# WPT_Round_2_RX_Schematics.net
KiCad netlist of a schematic drawn in Altium Designer
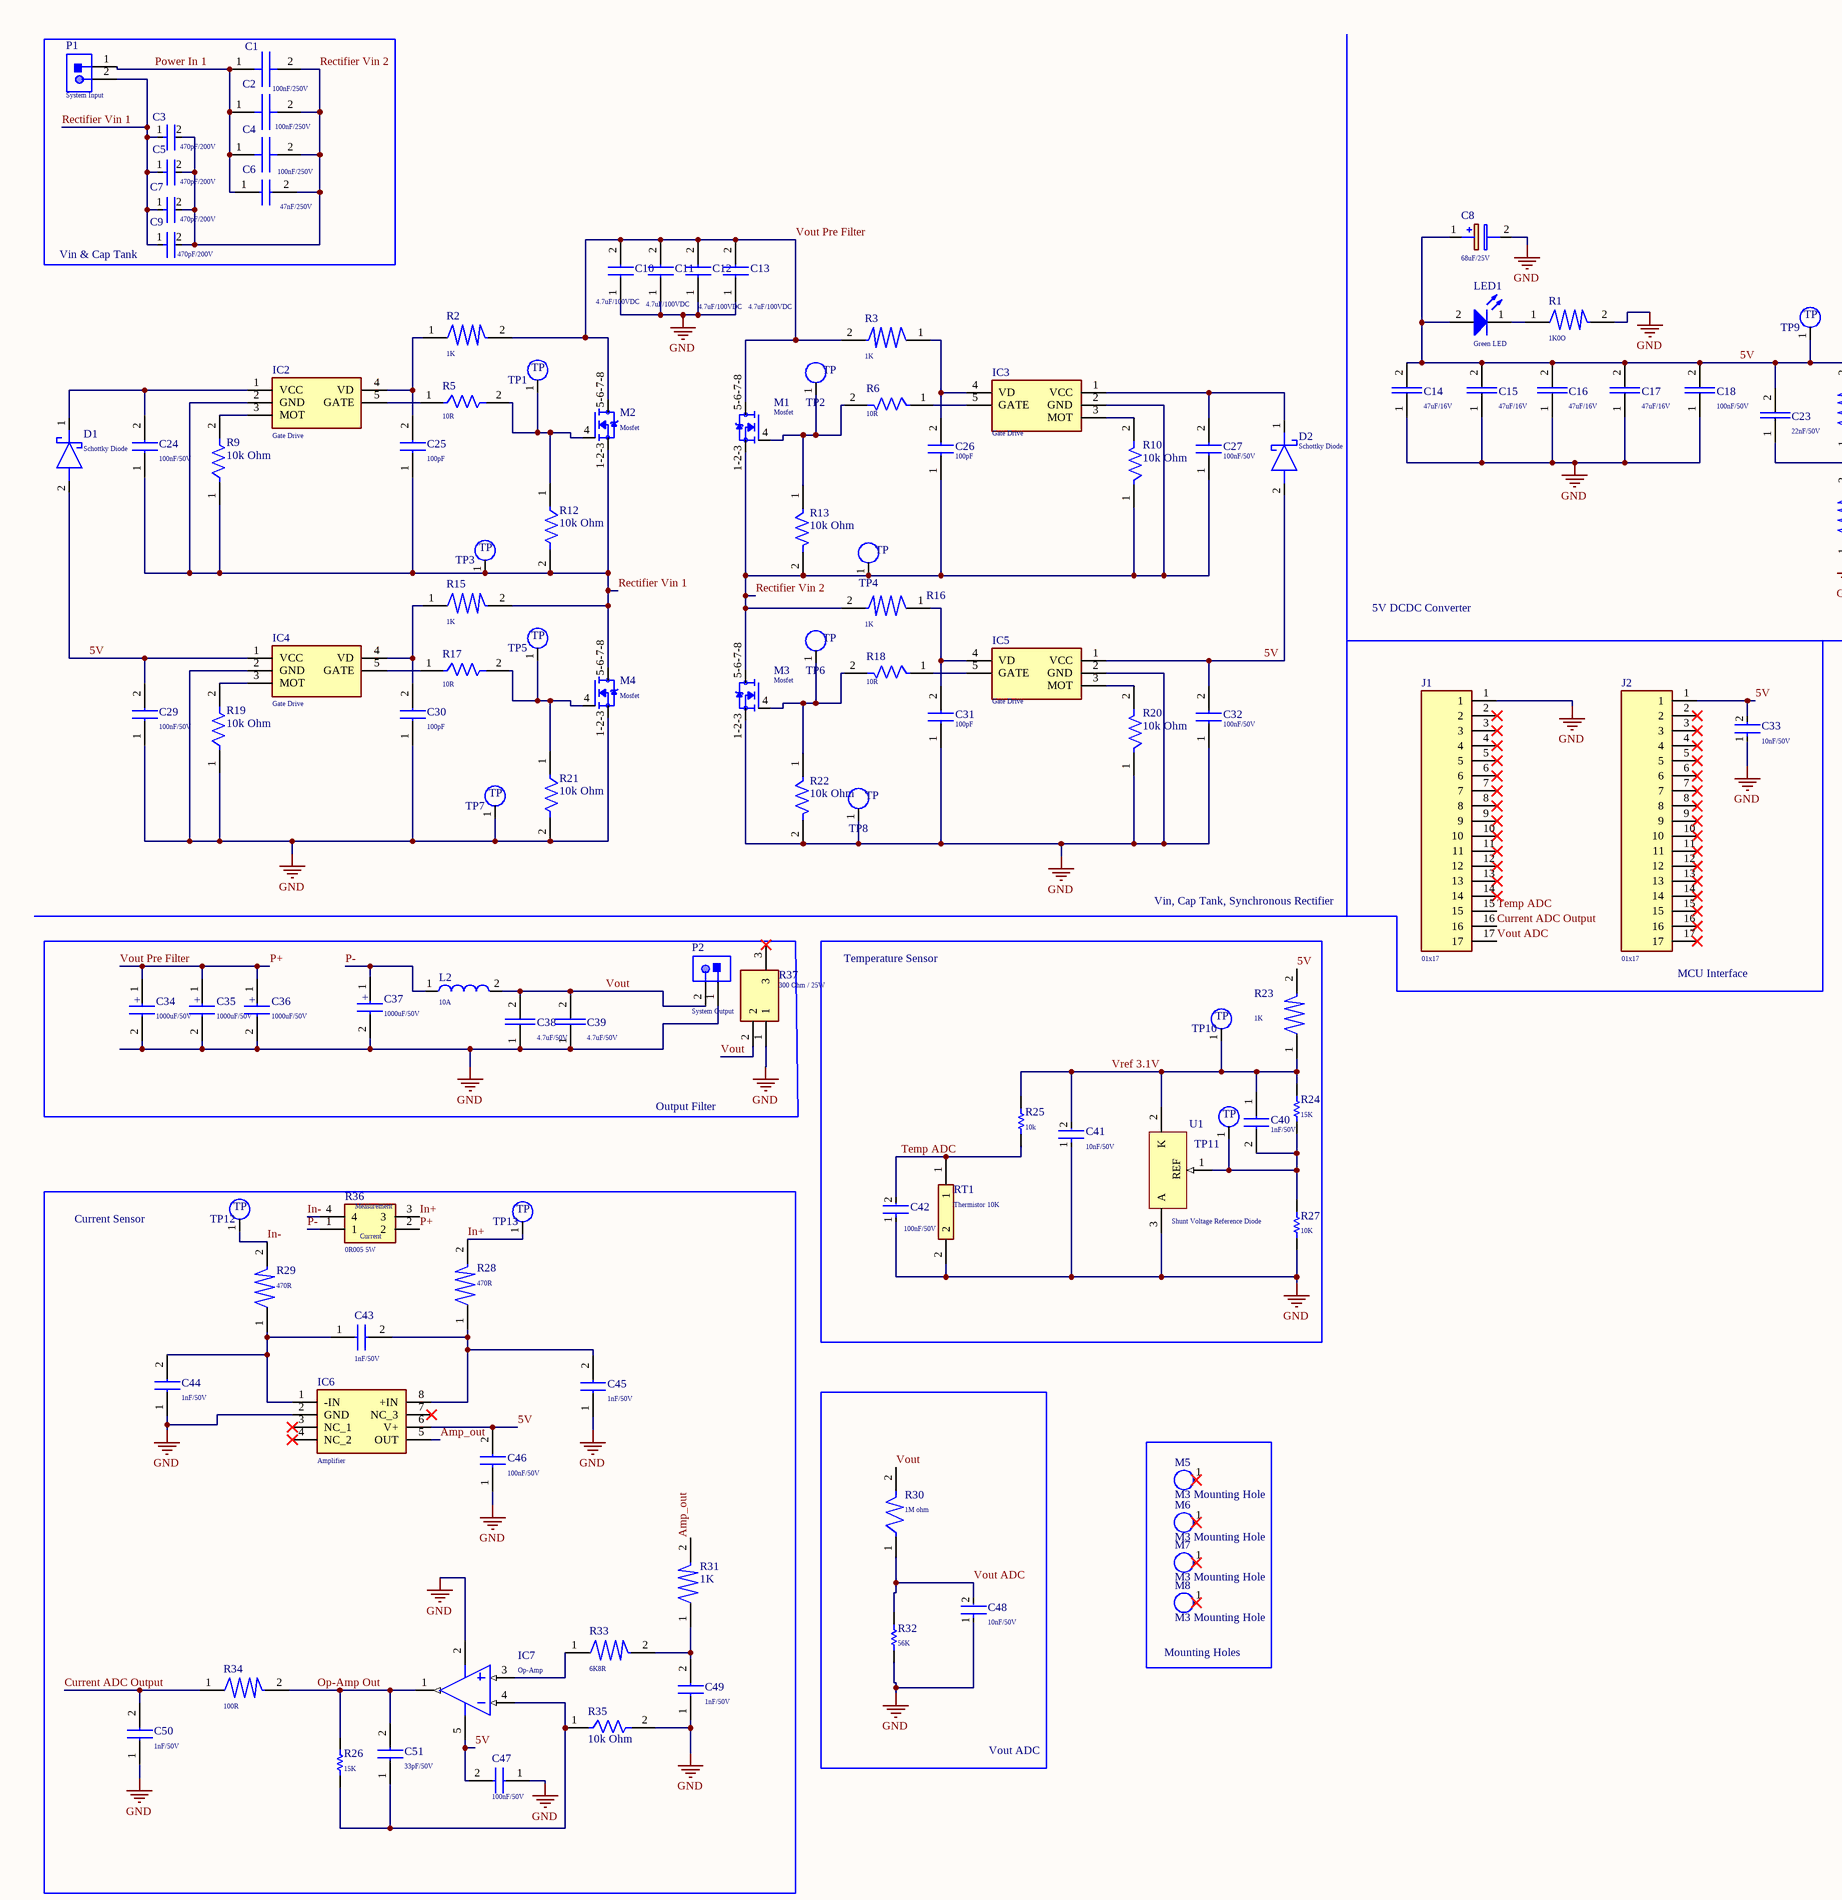
[diagram p0: WPT Round 2 RX Schematics.SchDoc, left]
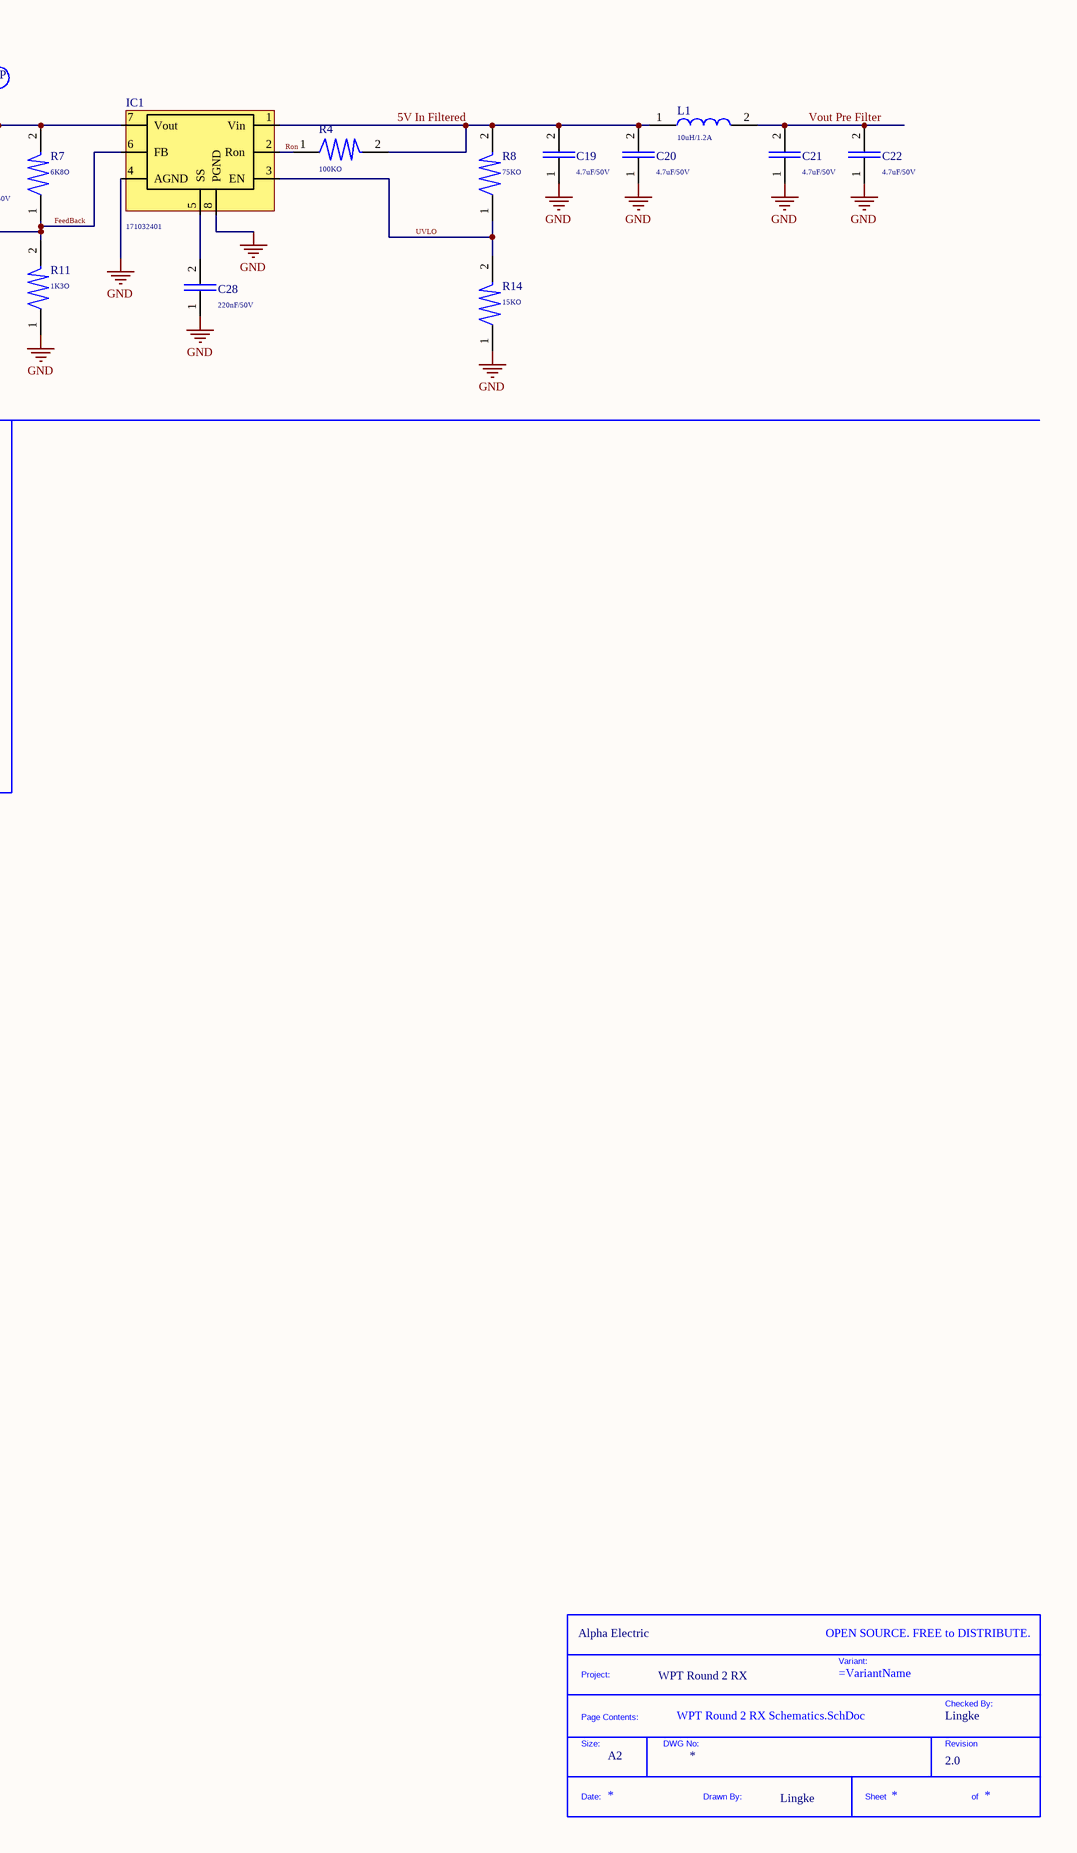
[diagram p1: WPT Round 2 RX Schematics.SchDoc, right]

(export (version "E")
  (design (tool "Eeschema 10.0.6"))
  (components
    (comp (ref "*")
      (value "Title_Block")
      (description "Standard Title Block.")
      (fields
        (field (name "PROJECT NAME") "WPT Round 2 RX")
        (field (name "COMPANY") "Alpha Electric")
        (field (name "DRAWN BY") "Lingke")
        (field (name "REVISION") "2.0")
        (field (name "DWG NO") "*")
        (field (name "SIZE") "A2")
        (field (name "CHECKED BY") "Lingke")
      )
      (libsource (lib "Symbol Library") (part "Title_Block"))
    )
    (comp (ref "C1")
      (value "100nF/250V")
      (footprint "SamacSys:CAPC4532X220N")
      (fields (field (name "MANUFACTURER_PART_NUMBER") "C1812C104JAGACAUTO"))
      (libsource (lib "Symbol Library") (part "C1812C104JAGACAUTO"))
    )
    (comp (ref "C2")
      (value "100nF/250V")
      (footprint "SamacSys:CAPC4532X220N")
      (fields (field (name "MANUFACTURER_PART_NUMBER") "C1812C104JAGACAUTO"))
      (libsource (lib "Symbol Library") (part "C1812C104JAGACAUTO"))
    )
    (comp (ref "C3")
      (value "470pF/200V")
      (footprint "FP-C1206C-EB-MFG")
      (description "CAP CER 470PF 200V 10% NP0 1206")
      (fields
        (field (name "OCTOPART") "https://octopart.com/c1206c471k2gactu-kemet-3658280")
        (field (name "TOLERANCE") "0.1")
      )
      (libsource (lib "Symbol Library") (part "C1206C471K2GACTU"))
    )
    (comp (ref "C4")
      (value "100nF/250V")
      (footprint "SamacSys:CAPC4532X220N")
      (fields (field (name "MANUFACTURER_PART_NUMBER") "C1812C104JAGACAUTO"))
      (libsource (lib "Symbol Library") (part "C1812C104JAGACAUTO"))
    )
    (comp (ref "C5")
      (value "470pF/200V")
      (footprint "FP-C1206C-EB-MFG")
      (description "CAP CER 470PF 200V 10% NP0 1206")
      (fields
        (field (name "OCTOPART") "https://octopart.com/c1206c471k2gactu-kemet-3658280")
        (field (name "TOLERANCE") "0.1")
      )
      (libsource (lib "Symbol Library") (part "C1206C471K2GACTU"))
    )
    (comp (ref "C6")
      (value "47nF/250V")
      (footprint "SamacSys:CAPC4532X350N")
      (description "Capacitor\r\n47nF/250V \r\nC0G")
      (fields (field (name "MANUFACTURER_PART_NUMBER") "C4532C0G2E473J320KA"))
      (libsource (lib "Symbol Library") (part "C4532C0G2E473J320KA"))
    )
    (comp (ref "C7")
      (value "470pF/200V")
      (footprint "FP-C1206C-EB-MFG")
      (description "CAP CER 470PF 200V 10% NP0 1206")
      (fields
        (field (name "OCTOPART") "https://octopart.com/c1206c471k2gactu-kemet-3658280")
        (field (name "TOLERANCE") "0.1")
      )
      (libsource (lib "Symbol Library") (part "C1206C471K2GACTU"))
    )
    (comp (ref "C8")
      (value "68uF/25V")
      (footprint "SamacSys:CAPAE830X1170N")
      (description "Capacitor Polarised")
      (fields (field (name "MANUFACTURER_PART_NUMBER") "875075555003"))
      (libsource (lib "Symbol Library") (part "875075555003"))
    )
    (comp (ref "C9")
      (value "470pF/200V")
      (footprint "FP-C1206C-EB-MFG")
      (description "CAP CER 470PF 200V 10% NP0 1206")
      (fields
        (field (name "OCTOPART") "https://octopart.com/c1206c471k2gactu-kemet-3658280")
        (field (name "TOLERANCE") "0.1")
      )
      (libsource (lib "Symbol Library") (part "C1206C471K2GACTU"))
    )
    (comp (ref "C10")
      (value "4.7uF/100VDC")
      (footprint "SamacSys:CAPC3225X280N")
      (fields
        (field (name "MOUSER2 PART NUMBER") "810-CNC6P1X7R2A475K2")
        (field (name "MANUFACTURER_PART_NUMBER") "CNC6P1X7R2A475K250AE")
      )
      (libsource (lib "Symbol Library") (part "CNC6P1X7R2A475K250AE"))
    )
    (comp (ref "C11")
      (value "4.7uF/100VDC")
      (footprint "SamacSys:CAPC3225X280N")
      (fields
        (field (name "MOUSER2 PART NUMBER") "810-CNC6P1X7R2A475K2")
        (field (name "MANUFACTURER_PART_NUMBER") "CNC6P1X7R2A475K250AE")
      )
      (libsource (lib "Symbol Library") (part "CNC6P1X7R2A475K250AE"))
    )
    (comp (ref "C12")
      (value "4.7uF/100VDC")
      (footprint "SamacSys:CAPC3225X280N")
      (fields
        (field (name "MOUSER2 PART NUMBER") "810-CNC6P1X7R2A475K2")
        (field (name "MANUFACTURER_PART_NUMBER") "CNC6P1X7R2A475K250AE")
      )
      (libsource (lib "Symbol Library") (part "CNC6P1X7R2A475K250AE"))
    )
    (comp (ref "C13")
      (value "4.7uF/100VDC")
      (footprint "SamacSys:CAPC3225X280N")
      (fields
        (field (name "MOUSER2 PART NUMBER") "810-CNC6P1X7R2A475K2")
        (field (name "MANUFACTURER_PART_NUMBER") "CNC6P1X7R2A475K250AE")
      )
      (libsource (lib "Symbol Library") (part "CNC6P1X7R2A475K250AE"))
    )
    (comp (ref "C14")
      (value "47uF/16V")
      (footprint "SamacSys:CAPC3225X280N")
      (description "Capacitor 47uF/16V")
      (libsource (lib "Symbol Library") (part "EMK325ABJ476MMHP"))
    )
    (comp (ref "C15")
      (value "47uF/16V")
      (footprint "SamacSys:CAPC3225X280N")
      (description "Capacitor 47uF/16V")
      (libsource (lib "Symbol Library") (part "EMK325ABJ476MMHP"))
    )
    (comp (ref "C16")
      (value "47uF/16V")
      (footprint "SamacSys:CAPC3225X280N")
      (description "Capacitor 47uF/16V")
      (libsource (lib "Symbol Library") (part "EMK325ABJ476MMHP"))
    )
    (comp (ref "C17")
      (value "47uF/16V")
      (footprint "SamacSys:CAPC3225X280N")
      (description "Capacitor 47uF/16V")
      (libsource (lib "Symbol Library") (part "EMK325ABJ476MMHP"))
    )
    (comp (ref "C18")
      (value "100nF/50V")
      (footprint "SamacSys:CAPC3216X90N")
      (description "Capacitor 100nF/50V")
      (fields
        (field (name "MOUSER2 PART NUMBER") "710-885012208087")
        (field (name "MANUFACTURER_PART_NUMBER") "885012208087")
      )
      (libsource (lib "Symbol Library") (part "885012208087"))
    )
    (comp (ref "C19")
      (value "4.7uF/50V")
      (footprint "SamacSys:CAPC3225X280N")
      (description "Capacitor 4.7uF/50V")
      (fields (field (name "MANUFACTURER_PART_NUMBER") "885012209048"))
      (libsource (lib "Symbol Library") (part "885012209048"))
    )
    (comp (ref "C20")
      (value "4.7uF/50V")
      (footprint "SamacSys:CAPC3225X280N")
      (description "Capacitor 4.7uF/50V")
      (fields (field (name "MANUFACTURER_PART_NUMBER") "885012209048"))
      (libsource (lib "Symbol Library") (part "885012209048"))
    )
    (comp (ref "C21")
      (value "4.7uF/50V")
      (footprint "SamacSys:CAPC3225X280N")
      (description "Capacitor 4.7uF/50V")
      (fields (field (name "MANUFACTURER_PART_NUMBER") "885012209048"))
      (libsource (lib "Symbol Library") (part "885012209048"))
    )
    (comp (ref "C22")
      (value "4.7uF/50V")
      (footprint "SamacSys:CAPC3225X280N")
      (description "Capacitor 4.7uF/50V")
      (fields (field (name "MANUFACTURER_PART_NUMBER") "885012209048"))
      (libsource (lib "Symbol Library") (part "885012209048"))
    )
    (comp (ref "C23")
      (value "22nF/50V")
      (footprint "SamacSys:CAPC2012X90N")
      (description "Capacitor 22nF/50V")
      (fields
        (field (name "MOUSER2 PART NUMBER") "710-885012207094")
        (field (name "MANUFACTURER_PART_NUMBER") "885012207094")
      )
      (libsource (lib "Symbol Library") (part "885012207094"))
    )
    (comp (ref "C24")
      (value "100nF/50V")
      (footprint "SamacSys:CAPC2012X90N")
      (description "Capacitor 100nF/50V")
      (fields
        (field (name "MOUSER2 PART NUMBER") "710-885012207098")
        (field (name "MANUFACTURER_PART_NUMBER") "885012207098")
      )
      (libsource (lib "") (part "885012207098_1"))
    )
    (comp (ref "C25")
      (value "100pF")
      (footprint "SamacSys:CAPC2012X70N")
      (description "Capacitor 100pF")
      (fields (field (name "MANUFACTURER_PART_NUMBER") "885012007057"))
      (libsource (lib "") (part "885012007057_1"))
    )
    (comp (ref "C26")
      (value "100pF")
      (footprint "SamacSys:CAPC2012X70N")
      (description "Capacitor 100pF")
      (fields (field (name "MANUFACTURER_PART_NUMBER") "885012007057"))
      (libsource (lib "") (part "885012007057_1"))
    )
    (comp (ref "C27")
      (value "100nF/50V")
      (footprint "SamacSys:CAPC2012X90N")
      (description "Capacitor 100nF/50V")
      (fields
        (field (name "MOUSER2 PART NUMBER") "710-885012207098")
        (field (name "MANUFACTURER_PART_NUMBER") "885012207098")
      )
      (libsource (lib "") (part "885012207098_1"))
    )
    (comp (ref "C28")
      (value "220nF/50V")
      (footprint "SamacSys:CAPC2012X90N")
      (description "Capacitor 220nF / 50V")
      (libsource (lib "Symbol Library") (part "885012207100"))
    )
    (comp (ref "C29")
      (value "100nF/50V")
      (footprint "SamacSys:CAPC2012X90N")
      (description "Capacitor 100nF/50V")
      (fields
        (field (name "MOUSER2 PART NUMBER") "710-885012207098")
        (field (name "MANUFACTURER_PART_NUMBER") "885012207098")
      )
      (libsource (lib "Symbol Library") (part "885012207098"))
    )
    (comp (ref "C30")
      (value "100pF")
      (footprint "SamacSys:CAPC2012X70N")
      (description "Capacitor 100pF")
      (fields (field (name "MANUFACTURER_PART_NUMBER") "885012007057"))
      (libsource (lib "Symbol Library") (part "885012007057"))
    )
    (comp (ref "C31")
      (value "100pF")
      (footprint "SamacSys:CAPC2012X70N")
      (description "Capacitor 100pF")
      (fields (field (name "MANUFACTURER_PART_NUMBER") "885012007057"))
      (libsource (lib "Symbol Library") (part "885012007057"))
    )
    (comp (ref "C32")
      (value "100nF/50V")
      (footprint "SamacSys:CAPC2012X90N")
      (description "Capacitor 100nF/50V")
      (fields
        (field (name "MOUSER2 PART NUMBER") "710-885012207098")
        (field (name "MANUFACTURER_PART_NUMBER") "885012207098")
      )
      (libsource (lib "Symbol Library") (part "885012207098"))
    )
    (comp (ref "C33")
      (value "10nF/50V")
      (footprint "0805 Capacitor")
      (libsource (lib "") (part "885012207092_2"))
    )
    (comp (ref "C34")
      (value "1000uF/50V")
      (footprint "SamacSys:CAPPRD500W62D1300H2650")
      (description "Capacitor 1000uF")
      (libsource (lib "Symbol Library") (part "ESH108M050AL4AA"))
    )
    (comp (ref "C35")
      (value "1000uF/50V")
      (footprint "SamacSys:CAPPRD500W62D1300H2650")
      (description "Capacitor 1000uF")
      (libsource (lib "Symbol Library") (part "ESH108M050AL4AA"))
    )
    (comp (ref "C36")
      (value "1000uF/50V")
      (footprint "SamacSys:CAPPRD500W62D1300H2650")
      (description "Capacitor 1000uF")
      (libsource (lib "Symbol Library") (part "ESH108M050AL4AA"))
    )
    (comp (ref "C37")
      (value "1000uF/50V")
      (footprint "SamacSys:CAPPRD500W62D1300H2650")
      (description "Capacitor 1000uF")
      (libsource (lib "Symbol Library") (part "ESH108M050AL4AA"))
    )
    (comp (ref "C38")
      (value "4.7uF/50V")
      (footprint "SamacSys:CAPC3225X280N")
      (description "Capacitor 4.7uF/50V")
      (fields (field (name "MANUFACTURER_PART_NUMBER") "885012209048"))
      (libsource (lib "") (part "885012209048_1"))
    )
    (comp (ref "C39")
      (value "4.7uF/50V")
      (footprint "SamacSys:CAPC3225X280N")
      (description "Capacitor 4.7uF/50V")
      (fields (field (name "MANUFACTURER_PART_NUMBER") "885012209048"))
      (libsource (lib "") (part "885012209048_1"))
    )
    (comp (ref "C40")
      (value "1nF/50V")
      (footprint "SamacSys:CAPC2012X90N")
      (fields (field (name "MANUFACTURER_PART_NUMBER") "885012207086"))
      (libsource (lib "Symbol Library") (part "885012207086"))
    )
    (comp (ref "C41")
      (value "10nF/50V")
      (footprint "0805 Capacitor")
      (libsource (lib "") (part "885012207092_1"))
    )
    (comp (ref "C42")
      (value "100nF/50V")
      (footprint "0805 Capacitor")
      (libsource (lib "") (part "885012207098_3"))
    )
    (comp (ref "C43")
      (value "1nF/50V")
      (footprint "SamacSys:CAPC2012X90N")
      (fields (field (name "MANUFACTURER_PART_NUMBER") "885012207086"))
      (libsource (lib "Symbol Library") (part "885012207086"))
    )
    (comp (ref "C44")
      (value "1nF/50V")
      (footprint "SamacSys:CAPC2012X90N")
      (fields (field (name "MANUFACTURER_PART_NUMBER") "885012207086"))
      (libsource (lib "Symbol Library") (part "885012207086"))
    )
    (comp (ref "C45")
      (value "1nF/50V")
      (footprint "SamacSys:CAPC2012X90N")
      (fields (field (name "MANUFACTURER_PART_NUMBER") "885012207086"))
      (libsource (lib "Symbol Library") (part "885012207086"))
    )
    (comp (ref "C46")
      (value "100nF/50V")
      (footprint "SamacSys:CAPC2012X90N")
      (libsource (lib "") (part "885012207098_2"))
    )
    (comp (ref "C47")
      (value "100nF/50V")
      (footprint "SamacSys:CAPC2012X90N")
      (libsource (lib "") (part "885012207098_2"))
    )
    (comp (ref "C48")
      (value "10nF/50V")
      (footprint "0805 Capacitor")
      (libsource (lib "Symbol Library") (part "885012207092"))
    )
    (comp (ref "C49")
      (value "1nF/50V")
      (footprint "SamacSys:CAPC2012X90N")
      (fields (field (name "MANUFACTURER_PART_NUMBER") "885012207086"))
      (libsource (lib "Symbol Library") (part "885012207086"))
    )
    (comp (ref "C50")
      (value "1nF/50V")
      (footprint "SamacSys:CAPC2012X90N")
      (fields (field (name "MANUFACTURER_PART_NUMBER") "885012207086"))
      (libsource (lib "Symbol Library") (part "885012207086"))
    )
    (comp (ref "C51")
      (value "33pF/50V")
      (footprint "CAPC2012X90N")
      (description "Capacitor 33pF/50V")
      (fields (field (name "MANUFACTURER_PART_NUMBER") "C0805C330J5GACTU"))
      (libsource (lib "Symbol Library") (part "C0805C330J5GACTU"))
    )
    (comp (ref "D1")
      (value "Schottky Diode")
      (footprint "SamacSys:RB400VAM50TR")
      (fields
        (field (name "MOUSER2 PART NUMBER") "755-RB400VAM-50TR")
        (field (name "MANUFACTURER_PART_NUMBER") "RB400VAM-50TR")
      )
      (libsource (lib "Symbol Library") (part "RB400VAM-50TR"))
    )
    (comp (ref "D2")
      (value "Schottky Diode")
      (footprint "SamacSys:RB400VAM50TR")
      (fields
        (field (name "MOUSER2 PART NUMBER") "755-RB400VAM-50TR")
        (field (name "MANUFACTURER_PART_NUMBER") "RB400VAM-50TR")
      )
      (libsource (lib "Symbol Library") (part "RB400VAM-50TR"))
    )
    (comp (ref "IC1")
      (value "171032401")
      (footprint "7 PIN PFM")
      (description "MagI³C-VDRM Variable Step Down Regulator Module WE-VDRM , Ui=6-42V")
      (fields (field (name "MANUFACTURER") "Wuerth Elektronik"))
      (libsource (lib "Symbol Library") (part "171032401"))
    )
    (comp (ref "IC2")
      (value "Gate Drive")
      (footprint "SamacSys:SOT95P280X145-5N")
      (description "Gate Driver IC")
      (fields (field (name "MANUFACTURER_PART_NUMBER") "IR1161LTRPBF"))
      (libsource (lib "Symbol Library") (part "IR1161LTRPBF"))
    )
    (comp (ref "IC3")
      (value "Gate Drive")
      (footprint "SamacSys:SOT95P280X145-5N")
      (description "Gate Driver IC")
      (fields (field (name "MANUFACTURER_PART_NUMBER") "IR1161LTRPBF"))
      (libsource (lib "") (part "IR1161LTRPBF_1"))
    )
    (comp (ref "IC4")
      (value "Gate Drive")
      (footprint "SamacSys:SOT95P280X145-5N")
      (description "Gate Driver IC")
      (fields (field (name "MANUFACTURER_PART_NUMBER") "IR1161LTRPBF"))
      (libsource (lib "Symbol Library") (part "IR1161LTRPBF"))
    )
    (comp (ref "IC5")
      (value "Gate Drive")
      (footprint "SamacSys:SOT95P280X145-5N")
      (description "Gate Driver IC")
      (fields (field (name "MANUFACTURER_PART_NUMBER") "IR1161LTRPBF"))
      (libsource (lib "") (part "IR1161LTRPBF_1"))
    )
    (comp (ref "IC6")
      (value "Amplifier")
      (footprint "SamacSys:SOIC127P600X175-8N")
      (description "Integrated Circuit Amplifier")
      (fields (field (name "MANUFACTURER_PART_NUMBER") "AD8215YRZ"))
      (libsource (lib "Symbol Library") (part "AD8215YRZ"))
    )
    (comp (ref "IC7")
      (value "Op-Amp")
      (footprint "ADI-RJ-5_N")
      (fields
        (field (name "MANUFACTURER") "Analog Devices")
        (field (name "PARTNUMBER") "AD8031ARTZ-REEL7")
        (field (name "GENERIC PART NUMBER") "AD8031")
      )
      (libsource (lib "Symbol Library") (part "AD8031ARTZ-REEL7"))
    )
    (comp (ref "J1")
      (value "01x17")
      (footprint "SamacSys:RHDR17W76P0X254_1X17_4318X254X826P")
      (description "Connector 2.54mm")
      (fields (field (name "MANUFACTURER_PART_NUMBER") "929850-01-17-RA"))
      (libsource (lib "Symbol Library") (part "929850-01-17-RA"))
    )
    (comp (ref "J2")
      (value "01x17")
      (footprint "SamacSys:RHDR17W76P0X254_1X17_4318X254X826P")
      (description "Connector 2.54mm")
      (fields (field (name "MANUFACTURER_PART_NUMBER") "929850-01-17-RA"))
      (libsource (lib "Symbol Library") (part "929850-01-17-RA"))
    )
    (comp (ref "L1")
      (value "10uH/1.2A")
      (footprint "SamacSys:WE-MAPI_3020")
      (description "Inductor")
      (fields (field (name "MANUFACTURER_PART_NUMBER") "74438336100"))
      (libsource (lib "Symbol Library") (part "74438336100"))
    )
    (comp (ref "L2")
      (value "10A")
      (footprint "WE-PF_1280")
      (description "SMD EMI Suppression Power Ferrite WE-PF, Z = 2900 Ohm")
      (libsource (lib "Symbol Library") (part "742792901"))
    )
    (comp (ref "LED1")
      (value "Green LED")
      (footprint "0805_A")
      (description "SMD mono-color Chip LED, WL-SMCW, Green")
      (fields (field (name "PARTNUMBER") "150080GS75000") (field (name "MANUFACTURER") "Wuerth Elektronik"))
      (libsource (lib "Symbol Library") (part "150080GS75000"))
    )
    (comp (ref "M1")
      (value "Mosfet")
      (footprint "Footprint Library:TRANS_BSZ037N06LS5ATMA1")
      (fields (field (name "MP") "BSZ037N06LS5ATMA1") (field (name "MF") "Infineon Technologies"))
      (libsource (lib "Symbol Library") (part "BSZ070N08LS5ATMA1"))
    )
    (comp (ref "M2")
      (value "Mosfet")
      (footprint "Footprint Library:TRANS_BSZ037N06LS5ATMA1")
      (fields (field (name "MP") "BSZ037N06LS5ATMA1") (field (name "MF") "Infineon Technologies"))
      (libsource (lib "Symbol Library") (part "BSZ070N08LS5ATMA1"))
    )
    (comp (ref "M3")
      (value "Mosfet")
      (footprint "Footprint Library:TRANS_BSZ037N06LS5ATMA1")
      (fields (field (name "MP") "BSZ037N06LS5ATMA1") (field (name "MF") "Infineon Technologies"))
      (libsource (lib "Symbol Library") (part "BSZ070N08LS5ATMA1"))
    )
    (comp (ref "M4")
      (value "Mosfet")
      (footprint "Footprint Library:TRANS_BSZ037N06LS5ATMA1")
      (fields (field (name "MP") "BSZ037N06LS5ATMA1") (field (name "MF") "Infineon Technologies"))
      (libsource (lib "Symbol Library") (part "BSZ070N08LS5ATMA1"))
    )
    (comp (ref "M5")
      (value "M3 Mounting Hole")
      (footprint "M3 Hole")
      (libsource (lib "Symbol Library") (part "M3_Mounting_hole"))
    )
    (comp (ref "M6")
      (value "M3 Mounting Hole")
      (footprint "M3 Hole")
      (libsource (lib "Symbol Library") (part "M3_Mounting_hole"))
    )
    (comp (ref "M7")
      (value "M3 Mounting Hole")
      (footprint "M3 Hole")
      (libsource (lib "Symbol Library") (part "M3_Mounting_hole"))
    )
    (comp (ref "M8")
      (value "M3 Mounting Hole")
      (footprint "M3 Hole")
      (libsource (lib "Symbol Library") (part "M3_Mounting_hole"))
    )
    (comp (ref "P1")
      (value "System Input")
      (footprint "691313510002")
      (description "Serie 313 - 5.08mm Close Horizontal PCB Header WR-TBL, 2 pin")
      (fields
        (field (name "PART NUMBER") "691313510002")
        (field (name "MANUFACTURER") "Wurth Elektronik")
        (field (name "PUBLISHER") "WurthElektronik")
      )
      (libsource (lib "Symbol Library") (part "691313510002"))
    )
    (comp (ref "P2")
      (value "System Output")
      (footprint "691313510002")
      (description "Serie 313 - 5.08mm Close Horizontal PCB Header WR-TBL, 2 pin")
      (fields
        (field (name "PART NUMBER") "691313510002")
        (field (name "MANUFACTURER") "Wurth Elektronik")
        (field (name "PUBLISHER") "WurthElektronik")
      )
      (libsource (lib "") (part "691313510002_1"))
    )
    (comp (ref "R1")
      (value "1K0O")
      (footprint "FP-CRCW0805-e3-MFG")
      (description "Resistor 1K0 Ohm")
      (libsource (lib "Symbol Library") (part "CRCW08051K00FKEAC"))
    )
    (comp (ref "R2")
      (value "1K")
      (footprint "FP-CRCW0805-e3-MFG")
      (description "Resistor 1k Ohm")
      (libsource (lib "Symbol Library") (part "CRCW08051K00FKEA"))
    )
    (comp (ref "R3")
      (value "1K")
      (footprint "FP-CRCW0805-e3-MFG")
      (description "Resistor 1k Ohm")
      (libsource (lib "Symbol Library") (part "CRCW08051K00FKEA"))
    )
    (comp (ref "R4")
      (value "100KO")
      (footprint "FP-CRCW0805-e3-MFG")
      (description "Resistor 100K Ohm")
      (libsource (lib "Symbol Library") (part "CRCW0805100KFKEB"))
    )
    (comp (ref "R5")
      (value "10R")
      (footprint "FP-CRCW1206-e3-IPC_A")
      (description "RES Thick Film, 10Ω, 1%, 0.25W, 100ppm/°C, 1206\r\nMOSFET Gate Resistor 10Ohm")
      (fields (field (name "TOLERANCE") "1%"))
      (libsource (lib "Symbol Library") (part "CRCW120610R0FKEA"))
    )
    (comp (ref "R6")
      (value "10R")
      (footprint "FP-CRCW1206-e3-IPC_A")
      (description "RES Thick Film, 10Ω, 1%, 0.25W, 100ppm/°C, 1206\r\nMOSFET Gate Resistor 10Ohm")
      (fields (field (name "TOLERANCE") "1%"))
      (libsource (lib "Symbol Library") (part "CRCW120610R0FKEA"))
    )
    (comp (ref "R7")
      (value "6K8O")
      (footprint "FP-CRCW0805-e3-MFG")
      (description "Resistor 6K8 Ohm")
      (libsource (lib "Symbol Library") (part "CRCW08056K80FKEA"))
    )
    (comp (ref "R8")
      (value "75KO")
      (footprint "FP-CRCW0805-e3-MFG")
      (description "Resistor 75K Ohm")
      (libsource (lib "Symbol Library") (part "CRCW080575K0FKEB"))
    )
    (comp (ref "R9")
      (value "10k Ohm")
      (footprint "0805 Resistor")
      (description "RES Thick Film, 10kΩ, 1%, 0.125W, 100ppm/°C, 0805\r\n10k Ohm")
      (fields (field (name "TOLERANCE") "1%"))
      (libsource (lib "Symbol Library") (part "CRCW080510K0FKEA"))
    )
    (comp (ref "R10")
      (value "10k Ohm")
      (footprint "0805 Resistor")
      (description "RES Thick Film, 10kΩ, 1%, 0.125W, 100ppm/°C, 0805\r\n10k Ohm")
      (fields (field (name "TOLERANCE") "1%"))
      (libsource (lib "Symbol Library") (part "CRCW080510K0FKEA"))
    )
    (comp (ref "R11")
      (value "1K3O")
      (footprint "FP-CRCW0805-e3-MFG")
      (description "Resistor 1K3 Ohm")
      (libsource (lib "Symbol Library") (part "CRCW08051K30FKEB"))
    )
    (comp (ref "R12")
      (value "10k Ohm")
      (footprint "0805 Resistor")
      (description "RES Thick Film, 10kΩ, 1%, 0.125W, 100ppm/°C, 0805\r\n10k Ohm")
      (fields (field (name "TOLERANCE") "1%"))
      (libsource (lib "Symbol Library") (part "CRCW080510K0FKEA"))
    )
    (comp (ref "R13")
      (value "10k Ohm")
      (footprint "0805 Resistor")
      (description "RES Thick Film, 10kΩ, 1%, 0.125W, 100ppm/°C, 0805\r\n10k Ohm")
      (fields (field (name "TOLERANCE") "1%"))
      (libsource (lib "Symbol Library") (part "CRCW080510K0FKEA"))
    )
    (comp (ref "R14")
      (value "15KO")
      (footprint "FP-CRCW0805-e3-MFG")
      (description "Resistor 15K Ohm")
      (libsource (lib "Symbol Library") (part "CRCW080515K0FKEB"))
    )
    (comp (ref "R15")
      (value "1K")
      (footprint "FP-CRCW0805-e3-MFG")
      (description "Resistor 1k Ohm")
      (libsource (lib "Symbol Library") (part "CRCW08051K00FKEA"))
    )
    (comp (ref "R16")
      (value "1K")
      (footprint "FP-CRCW0805-e3-MFG")
      (description "Resistor 1k Ohm")
      (libsource (lib "Symbol Library") (part "CRCW08051K00FKEA"))
    )
    (comp (ref "R17")
      (value "10R")
      (footprint "FP-CRCW1206-e3-IPC_A")
      (description "RES Thick Film, 10Ω, 1%, 0.25W, 100ppm/°C, 1206\r\nMOSFET Gate Resistor 10Ohm")
      (fields (field (name "TOLERANCE") "1%"))
      (libsource (lib "Symbol Library") (part "CRCW120610R0FKEA"))
    )
    (comp (ref "R18")
      (value "10R")
      (footprint "FP-CRCW1206-e3-IPC_A")
      (description "RES Thick Film, 10Ω, 1%, 0.25W, 100ppm/°C, 1206\r\nMOSFET Gate Resistor 10Ohm")
      (fields (field (name "TOLERANCE") "1%"))
      (libsource (lib "Symbol Library") (part "CRCW120610R0FKEA"))
    )
    (comp (ref "R19")
      (value "10k Ohm")
      (footprint "0805 Resistor")
      (description "RES Thick Film, 10kΩ, 1%, 0.125W, 100ppm/°C, 0805\r\n10k Ohm")
      (fields (field (name "TOLERANCE") "1%"))
      (libsource (lib "") (part "CRCW080510K0FKEA_1"))
    )
    (comp (ref "R20")
      (value "10k Ohm")
      (footprint "0805 Resistor")
      (description "RES Thick Film, 10kΩ, 1%, 0.125W, 100ppm/°C, 0805\r\n10k Ohm")
      (fields (field (name "TOLERANCE") "1%"))
      (libsource (lib "") (part "CRCW080510K0FKEA_1"))
    )
    (comp (ref "R21")
      (value "10k Ohm")
      (footprint "0805 Resistor")
      (description "RES Thick Film, 10kΩ, 1%, 0.125W, 100ppm/°C, 0805\r\n10k Ohm")
      (fields (field (name "TOLERANCE") "1%"))
      (libsource (lib "Symbol Library") (part "CRCW080510K0FKEA"))
    )
    (comp (ref "R22")
      (value "10k Ohm")
      (footprint "0805 Resistor")
      (description "RES Thick Film, 10kΩ, 1%, 0.125W, 100ppm/°C, 0805\r\n10k Ohm")
      (fields (field (name "TOLERANCE") "1%"))
      (libsource (lib "Symbol Library") (part "CRCW080510K0FKEA"))
    )
    (comp (ref "R23")
      (value "1K")
      (footprint "FP-CRCW0805-e3-MFG")
      (description "Resistor 1k Ohm")
      (libsource (lib "Symbol Library") (part "CRCW08051K00FKEA"))
    )
    (comp (ref "R24")
      (value "15K")
      (footprint "0805 Resistor")
      (description "High Presicion 15K Ohm")
      (libsource (lib "Symbol Library") (part "ERA-6ARW153V"))
    )
    (comp (ref "R25")
      (value "10k")
      (footprint "0805 Resistor")
      (description "High Presition and High reliability 10K Ohm Resistor")
      (libsource (lib "Symbol Library") (part "ERA-6ARB103V"))
    )
    (comp (ref "R26")
      (value "15K")
      (footprint "0805 Resistor")
      (description "15K Ohm Resistor")
      (libsource (lib "Symbol Library") (part "ERA-6AED153V"))
    )
    (comp (ref "R27")
      (value "10K")
      (footprint "0805 Resistor")
      (description "High Presicion 10K Ohm")
      (libsource (lib "Symbol Library") (part "CRCW080510K0FKEB"))
    )
    (comp (ref "R28")
      (value "470R")
      (footprint "FP-CRCW0805-e3-MFG")
      (description "Resistor 470 Ohm")
      (libsource (lib "Symbol Library") (part "CRCW0805470RFKEB"))
    )
    (comp (ref "R29")
      (value "470R")
      (footprint "FP-CRCW0805-e3-MFG")
      (description "Resistor 470 Ohm")
      (libsource (lib "Symbol Library") (part "CRCW0805470RFKEB"))
    )
    (comp (ref "R30")
      (value "1M ohm")
      (footprint "FP-CRCW0805-e3-MFG")
      (description "RES Thick Film, 1MΩ, 1%, 0.125W, 100ppm/°C, 0805\r\n1M Ohm Resistor")
      (fields (field (name "TOLERANCE") "1%"))
      (libsource (lib "Symbol Library") (part "CRCW08051M00FKEA"))
    )
    (comp (ref "R31")
      (value "1K")
      (footprint "FP-CRCW0805-e3-MFG")
      (description "Resistor 1k Ohm")
      (libsource (lib "Symbol Library") (part "CRCW08051K00FKEA"))
    )
    (comp (ref "R32")
      (value "56K")
      (footprint "0805 Resistor")
      (description "56K Ohm Resistor")
      (libsource (lib "Symbol Library") (part "ERJ-6ENF5622V"))
    )
    (comp (ref "R33")
      (value "6K8R")
      (footprint "FP-CRCW0805-e3-MFG")
      (description "Resistor 6.8K Ohm")
      (libsource (lib "Symbol Library") (part "CRCW08056K80FKEA"))
    )
    (comp (ref "R34")
      (value "100R")
      (footprint "FP-CRCW0805-e3-MFG")
      (description "Resistor 100 Ohm")
      (libsource (lib "Symbol Library") (part "CRCW0805100RFKEB"))
    )
    (comp (ref "R35")
      (value "10k Ohm")
      (footprint "0805 Resistor")
      (description "RES Thick Film, 10kΩ, 1%, 0.125W, 100ppm/°C, 0805\r\n10k Ohm")
      (fields (field (name "TOLERANCE") "1%"))
      (libsource (lib "Symbol Library") (part "CRCW080510K0FKEA"))
    )
    (comp (ref "R36")
      (value "0R005 5W")
      (footprint "SamacSys:FC4L110R005FER")
      (description "Resistor 0R005 5W")
      (fields (field (name "MANUFACTURER_PART_NUMBER") "FC4L110R005FER"))
      (libsource (lib "Symbol Library") (part "FC4L110R005FER"))
    )
    (comp (ref "R37")
      (value "300 Ohm / 25W")
      (footprint "SamacSys:PWR163S253000FE")
      (description "Resistor 300 Ohm / 25W")
      (fields (field (name "MANUFACTURER_PART_NUMBER") "PWR163S-25-3000FE"))
      (libsource (lib "Symbol Library") (part "PWR163S-25-3000FE"))
    )
    (comp (ref "RT1")
      (value "Thermistor 10K")
      (footprint "SamacSys:THRMC2012X95N")
      (description "Thermistor 10Kohm B Parameter: 3950k")
      (fields (field (name "MANUFACTURER_PART_NUMBER") "NTCS0805E3103HMT"))
      (libsource (lib "Symbol Library") (part "NTCS0805E3103HMT"))
    )
    (comp (ref "TP1")
      (value "TP")
      (footprint "Test Point")
      (description "Test Point 1mm by 1mm")
      (libsource (lib "Symbol Library") (part "Test Point"))
    )
    (comp (ref "TP2")
      (value "TP")
      (footprint "Test Point")
      (description "Test Point 1mm by 1mm")
      (libsource (lib "Symbol Library") (part "Test Point"))
    )
    (comp (ref "TP3")
      (value "TP")
      (footprint "Test Point")
      (description "Test Point 1mm by 1mm")
      (libsource (lib "Symbol Library") (part "Test Point"))
    )
    (comp (ref "TP4")
      (value "TP")
      (footprint "Test Point")
      (description "Test Point 1mm by 1mm")
      (libsource (lib "Symbol Library") (part "Test Point"))
    )
    (comp (ref "TP5")
      (value "TP")
      (footprint "Test Point")
      (description "Test Point 1mm by 1mm")
      (libsource (lib "Symbol Library") (part "Test Point"))
    )
    (comp (ref "TP6")
      (value "TP")
      (footprint "Test Point")
      (description "Test Point 1mm by 1mm")
      (libsource (lib "Symbol Library") (part "Test Point"))
    )
    (comp (ref "TP7")
      (value "TP")
      (footprint "Test Point")
      (description "Test Point 1mm by 1mm")
      (libsource (lib "Symbol Library") (part "Test Point"))
    )
    (comp (ref "TP8")
      (value "TP")
      (footprint "Test Point")
      (description "Test Point 1mm by 1mm")
      (libsource (lib "Symbol Library") (part "Test Point"))
    )
    (comp (ref "TP9")
      (value "TP")
      (footprint "Test Point")
      (description "Test Point 1mm by 1mm")
      (libsource (lib "Symbol Library") (part "Test Point"))
    )
    (comp (ref "TP10")
      (value "TP")
      (footprint "Test Point")
      (description "Test Point 1mm by 1mm")
      (libsource (lib "Symbol Library") (part "Test Point"))
    )
    (comp (ref "TP11")
      (value "TP")
      (footprint "Test Point")
      (description "Test Point 1mm by 1mm")
      (libsource (lib "Symbol Library") (part "Test Point"))
    )
    (comp (ref "TP12")
      (value "TP")
      (footprint "Test Point")
      (description "Test Point 1mm by 1mm")
      (libsource (lib "Symbol Library") (part "Test Point"))
    )
    (comp (ref "TP13")
      (value "TP")
      (footprint "Test Point")
      (description "Test Point 1mm by 1mm")
      (libsource (lib "Symbol Library") (part "Test Point"))
    )
    (comp (ref "U1")
      (value "Shunt Voltage Reference Diode")
      (footprint "SOT23-3_N")
      (description "Shunt voltage reference, adjustable, 1.24 to 10V, 0.5% precision, 3-Pin SOT23-3L, Tape and Reel")
      (libsource (lib "Symbol Library") (part "TS432AILT"))
    )
  )
  (nets
    (net (code "1") (name "/5V") (class "Default")
      (node (ref "C14") (pin "2") (pinfunction "2_2") (pintype "passive"))
      (node (ref "C15") (pin "2") (pinfunction "2_2") (pintype "passive"))
      (node (ref "C16") (pin "2") (pinfunction "2_2") (pintype "passive"))
      (node (ref "C17") (pin "2") (pinfunction "2_2") (pintype "passive"))
      (node (ref "C18") (pin "2") (pinfunction "2_2") (pintype "passive"))
      (node (ref "C23") (pin "2") (pinfunction "2_2") (pintype "passive"))
      (node (ref "C29") (pin "2") (pinfunction "2_2") (pintype "passive"))
      (node (ref "C32") (pin "2") (pinfunction "2_2") (pintype "passive"))
      (node (ref "C33") (pin "2") (pinfunction "2_2") (pintype "passive"))
      (node (ref "C46") (pin "2") (pinfunction "2_2") (pintype "passive"))
      (node (ref "C47") (pin "2") (pinfunction "2_2") (pintype "passive"))
      (node (ref "C8") (pin "1") (pinfunction "+_1") (pintype "passive"))
      (node (ref "D1") (pin "2") (pinfunction "A_2") (pintype "passive"))
      (node (ref "D2") (pin "2") (pinfunction "A_2") (pintype "passive"))
      (node (ref "IC1") (pin "7") (pinfunction "Vout_7") (pintype "passive"))
      (node (ref "IC4") (pin "1") (pinfunction "VCC_1") (pintype "passive"))
      (node (ref "IC5") (pin "1") (pinfunction "VCC_1") (pintype "passive"))
      (node (ref "IC6") (pin "6") (pinfunction "V+_6") (pintype "passive"))
      (node (ref "IC7") (pin "5") (pinfunction "+VS_5") (pintype "power_in"))
      (node (ref "J2") (pin "1") (pinfunction "1_1") (pintype "passive"))
      (node (ref "LED1") (pin "2") (pinfunction "A_2") (pintype "passive"))
      (node (ref "R23") (pin "2") (pinfunction "2_2") (pintype "passive"))
      (node (ref "R7") (pin "2") (pinfunction "2_2") (pintype "passive"))
      (node (ref "TP9") (pin "1") (pinfunction "TP_1") (pintype "passive"))
    )
    (net (code "2") (name "/5V In Filtered") (class "Default")
      (node (ref "C19") (pin "2") (pinfunction "2_2") (pintype "passive"))
      (node (ref "C20") (pin "2") (pinfunction "2_2") (pintype "passive"))
      (node (ref "IC1") (pin "1") (pinfunction "Vin_1") (pintype "passive"))
      (node (ref "L1") (pin "1") (pinfunction "1_1") (pintype "passive"))
      (node (ref "R4") (pin "2") (pinfunction "2_2") (pintype "passive"))
      (node (ref "R8") (pin "2") (pinfunction "2_2") (pintype "passive"))
    )
    (net (code "3") (name "/Amp_out") (class "Default")
      (node (ref "IC6") (pin "5") (pinfunction "OUT_5") (pintype "passive"))
      (node (ref "R31") (pin "2") (pinfunction "2_2") (pintype "passive"))
    )
    (net (code "4") (name "/Current ADC Output") (class "Default")
      (node (ref "C50") (pin "2") (pinfunction "2_2") (pintype "passive"))
      (node (ref "J1") (pin "16") (pinfunction "16_16") (pintype "passive"))
      (node (ref "R34") (pin "1") (pinfunction "1_1") (pintype "passive"))
    )
    (net (code "5") (name "/FeedBack") (class "Default")
      (node (ref "C23") (pin "1") (pinfunction "1_1") (pintype "passive"))
      (node (ref "IC1") (pin "6") (pinfunction "FB_6") (pintype "passive"))
      (node (ref "R11") (pin "2") (pinfunction "2_2") (pintype "passive"))
      (node (ref "R7") (pin "1") (pinfunction "1_1") (pintype "passive"))
    )
    (net (code "6") (name "/In+") (class "Default")
      (node (ref "R28") (pin "2") (pinfunction "2_2") (pintype "passive"))
      (node (ref "R36") (pin "3") (pinfunction "3_3") (pintype "passive"))
      (node (ref "TP13") (pin "1") (pinfunction "TP_1") (pintype "passive"))
    )
    (net (code "7") (name "/In-") (class "Default")
      (node (ref "R29") (pin "2") (pinfunction "2_2") (pintype "passive"))
      (node (ref "R36") (pin "4") (pinfunction "4_4") (pintype "passive"))
      (node (ref "TP12") (pin "1") (pinfunction "TP_1") (pintype "passive"))
    )
    (net (code "8") (name "/Op-Amp Out") (class "Default")
      (node (ref "C51") (pin "2") (pinfunction "C2_2") (pintype "passive"))
      (node (ref "IC7") (pin "1") (pinfunction "VOUT_1") (pintype "output"))
      (node (ref "R26") (pin "2") (pinfunction "2_2") (pintype "passive"))
      (node (ref "R34") (pin "2") (pinfunction "2_2") (pintype "passive"))
    )
    (net (code "9") (name "/P+") (class "Default")
      (node (ref "C10") (pin "2") (pinfunction "2_2") (pintype "passive"))
      (node (ref "C11") (pin "2") (pinfunction "2_2") (pintype "passive"))
      (node (ref "C12") (pin "2") (pinfunction "2_2") (pintype "passive"))
      (node (ref "C13") (pin "2") (pinfunction "2_2") (pintype "passive"))
      (node (ref "C21") (pin "2") (pinfunction "2_2") (pintype "passive"))
      (node (ref "C22") (pin "2") (pinfunction "2_2") (pintype "passive"))
      (node (ref "C34") (pin "1") (pinfunction "+_1") (pintype "passive"))
      (node (ref "C35") (pin "1") (pinfunction "+_1") (pintype "passive"))
      (node (ref "C36") (pin "1") (pinfunction "+_1") (pintype "passive"))
      (node (ref "L1") (pin "2") (pinfunction "2_2") (pintype "passive"))
      (node (ref "M1") (pin "5-6-7-8") (pinfunction "D_5-6-7-8") (pintype "passive"))
      (node (ref "M2") (pin "5-6-7-8") (pinfunction "D_5-6-7-8") (pintype "passive"))
      (node (ref "R2") (pin "2") (pinfunction "2_2") (pintype "passive"))
      (node (ref "R3") (pin "2") (pinfunction "2_2") (pintype "passive"))
      (node (ref "R36") (pin "2") (pinfunction "2_2") (pintype "passive"))
    )
    (net (code "10") (name "/P-") (class "Default")
      (node (ref "C37") (pin "1") (pinfunction "+_1") (pintype "passive"))
      (node (ref "L2") (pin "1") (pinfunction "1_1") (pintype "passive"))
      (node (ref "R36") (pin "1") (pinfunction "1_1") (pintype "passive"))
    )
    (net (code "11") (name "/Power In 1") (class "Default")
      (node (ref "C1") (pin "1") (pinfunction "1_1") (pintype "passive"))
      (node (ref "C2") (pin "1") (pinfunction "1_1") (pintype "passive"))
      (node (ref "C4") (pin "1") (pinfunction "1_1") (pintype "passive"))
      (node (ref "C6") (pin "1") (pinfunction "1_1") (pintype "passive"))
      (node (ref "P1") (pin "1") (pinfunction "1_1") (pintype "passive"))
    )
    (net (code "12") (name "/Rectifier Vin 1") (class "Default")
      (node (ref "C24") (pin "1") (pinfunction "1_1") (pintype "passive"))
      (node (ref "C25") (pin "1") (pinfunction "1_1") (pintype "passive"))
      (node (ref "C3") (pin "1") (pinfunction "1_1") (pintype "passive"))
      (node (ref "C5") (pin "1") (pinfunction "1_1") (pintype "passive"))
      (node (ref "C7") (pin "1") (pinfunction "1_1") (pintype "passive"))
      (node (ref "C9") (pin "1") (pinfunction "1_1") (pintype "passive"))
      (node (ref "IC2") (pin "2") (pinfunction "GND_2") (pintype "passive"))
      (node (ref "M2") (pin "1-2-3") (pinfunction "S_1-2-3") (pintype "passive"))
      (node (ref "M4") (pin "5-6-7-8") (pinfunction "D_5-6-7-8") (pintype "passive"))
      (node (ref "P1") (pin "2") (pinfunction "2_2") (pintype "passive"))
      (node (ref "R12") (pin "2") (pinfunction "2_2") (pintype "passive"))
      (node (ref "R15") (pin "2") (pinfunction "2_2") (pintype "passive"))
      (node (ref "R9") (pin "1") (pinfunction "1_1") (pintype "passive"))
      (node (ref "TP3") (pin "1") (pinfunction "TP_1") (pintype "passive"))
    )
    (net (code "13") (name "/Rectifier Vin 2") (class "Default")
      (node (ref "C1") (pin "2") (pinfunction "2_2") (pintype "passive"))
      (node (ref "C2") (pin "2") (pinfunction "2_2") (pintype "passive"))
      (node (ref "C26") (pin "1") (pinfunction "1_1") (pintype "passive"))
      (node (ref "C27") (pin "1") (pinfunction "1_1") (pintype "passive"))
      (node (ref "C3") (pin "2") (pinfunction "2_2") (pintype "passive"))
      (node (ref "C4") (pin "2") (pinfunction "2_2") (pintype "passive"))
      (node (ref "C5") (pin "2") (pinfunction "2_2") (pintype "passive"))
      (node (ref "C6") (pin "2") (pinfunction "2_2") (pintype "passive"))
      (node (ref "C7") (pin "2") (pinfunction "2_2") (pintype "passive"))
      (node (ref "C9") (pin "2") (pinfunction "2_2") (pintype "passive"))
      (node (ref "IC3") (pin "2") (pinfunction "GND_2") (pintype "passive"))
      (node (ref "M1") (pin "1-2-3") (pinfunction "S_1-2-3") (pintype "passive"))
      (node (ref "M3") (pin "5-6-7-8") (pinfunction "D_5-6-7-8") (pintype "passive"))
      (node (ref "R10") (pin "1") (pinfunction "1_1") (pintype "passive"))
      (node (ref "R13") (pin "2") (pinfunction "2_2") (pintype "passive"))
      (node (ref "R16") (pin "2") (pinfunction "2_2") (pintype "passive"))
      (node (ref "TP4") (pin "1") (pinfunction "TP_1") (pintype "passive"))
    )
    (net (code "14") (name "/Ron") (class "Default")
      (node (ref "IC1") (pin "2") (pinfunction "Ron_2") (pintype "passive"))
      (node (ref "R4") (pin "1") (pinfunction "1_1") (pintype "passive"))
    )
    (net (code "15") (name "/Temp ADC") (class "Default")
      (node (ref "C42") (pin "2") (pinfunction "2_2") (pintype "passive"))
      (node (ref "J1") (pin "15") (pinfunction "15_15") (pintype "passive"))
      (node (ref "R25") (pin "1") (pinfunction "1_1") (pintype "passive"))
      (node (ref "RT1") (pin "1") (pinfunction "1_1") (pintype "passive"))
    )
    (net (code "16") (name "/UVLO") (class "Default")
      (node (ref "IC1") (pin "3") (pinfunction "EN_3") (pintype "passive"))
      (node (ref "R14") (pin "2") (pinfunction "2_2") (pintype "passive"))
      (node (ref "R8") (pin "1") (pinfunction "1_1") (pintype "passive"))
    )
    (net (code "17") (name "/Vout") (class "Default")
      (node (ref "C38") (pin "2") (pinfunction "2_2") (pintype "passive"))
      (node (ref "C39") (pin "2") (pinfunction "2_2") (pintype "passive"))
      (node (ref "L2") (pin "2") (pinfunction "2_2") (pintype "passive"))
      (node (ref "P2") (pin "2") (pinfunction "2_2") (pintype "passive"))
      (node (ref "R30") (pin "2") (pinfunction "2_2") (pintype "passive"))
      (node (ref "R37") (pin "2") (pinfunction "2_2") (pintype "passive"))
    )
    (net (code "18") (name "/Vout ADC") (class "Default")
      (node (ref "C48") (pin "2") (pinfunction "2_2") (pintype "passive"))
      (node (ref "J1") (pin "17") (pinfunction "17_17") (pintype "passive"))
      (node (ref "R30") (pin "1") (pinfunction "1_1") (pintype "passive"))
      (node (ref "R32") (pin "2") (pinfunction "2_2") (pintype "passive"))
    )
    (net (code "19") (name "/Vref 3.1V") (class "Default")
      (node (ref "C40") (pin "1") (pinfunction "1_1") (pintype "passive"))
      (node (ref "C41") (pin "2") (pinfunction "2_2") (pintype "passive"))
      (node (ref "R23") (pin "1") (pinfunction "1_1") (pintype "passive"))
      (node (ref "R24") (pin "2") (pinfunction "2_2") (pintype "passive"))
      (node (ref "R25") (pin "2") (pinfunction "2_2") (pintype "passive"))
      (node (ref "TP10") (pin "1") (pinfunction "TP_1") (pintype "passive"))
      (node (ref "U1") (pin "2") (pinfunction "K_2") (pintype "passive"))
    )
    (net (code "20") (name "GND") (class "Default")
      (node (ref "C10") (pin "1") (pinfunction "1_1") (pintype "passive"))
      (node (ref "C11") (pin "1") (pinfunction "1_1") (pintype "passive"))
      (node (ref "C12") (pin "1") (pinfunction "1_1") (pintype "passive"))
      (node (ref "C13") (pin "1") (pinfunction "1_1") (pintype "passive"))
      (node (ref "C14") (pin "1") (pinfunction "1_1") (pintype "passive"))
      (node (ref "C15") (pin "1") (pinfunction "1_1") (pintype "passive"))
      (node (ref "C16") (pin "1") (pinfunction "1_1") (pintype "passive"))
      (node (ref "C17") (pin "1") (pinfunction "1_1") (pintype "passive"))
      (node (ref "C18") (pin "1") (pinfunction "1_1") (pintype "passive"))
      (node (ref "C19") (pin "1") (pinfunction "1_1") (pintype "passive"))
      (node (ref "C20") (pin "1") (pinfunction "1_1") (pintype "passive"))
      (node (ref "C21") (pin "1") (pinfunction "1_1") (pintype "passive"))
      (node (ref "C22") (pin "1") (pinfunction "1_1") (pintype "passive"))
      (node (ref "C28") (pin "1") (pinfunction "1_1") (pintype "passive"))
      (node (ref "C29") (pin "1") (pinfunction "1_1") (pintype "passive"))
      (node (ref "C30") (pin "1") (pinfunction "1_1") (pintype "passive"))
      (node (ref "C31") (pin "1") (pinfunction "1_1") (pintype "passive"))
      (node (ref "C32") (pin "1") (pinfunction "1_1") (pintype "passive"))
      (node (ref "C33") (pin "1") (pinfunction "1_1") (pintype "passive"))
      (node (ref "C34") (pin "2") (pinfunction "-_2") (pintype "passive"))
      (node (ref "C35") (pin "2") (pinfunction "-_2") (pintype "passive"))
      (node (ref "C36") (pin "2") (pinfunction "-_2") (pintype "passive"))
      (node (ref "C37") (pin "2") (pinfunction "-_2") (pintype "passive"))
      (node (ref "C38") (pin "1") (pinfunction "1_1") (pintype "passive"))
      (node (ref "C39") (pin "1") (pinfunction "1_1") (pintype "passive"))
      (node (ref "C41") (pin "1") (pinfunction "1_1") (pintype "passive"))
      (node (ref "C42") (pin "1") (pinfunction "1_1") (pintype "passive"))
      (node (ref "C44") (pin "1") (pinfunction "1_1") (pintype "passive"))
      (node (ref "C45") (pin "1") (pinfunction "1_1") (pintype "passive"))
      (node (ref "C46") (pin "1") (pinfunction "1_1") (pintype "passive"))
      (node (ref "C47") (pin "1") (pinfunction "1_1") (pintype "passive"))
      (node (ref "C48") (pin "1") (pinfunction "1_1") (pintype "passive"))
      (node (ref "C49") (pin "1") (pinfunction "1_1") (pintype "passive"))
      (node (ref "C50") (pin "1") (pinfunction "1_1") (pintype "passive"))
      (node (ref "C8") (pin "2") (pinfunction "-_2") (pintype "passive"))
      (node (ref "IC1") (pin "4") (pinfunction "AGND_4") (pintype "passive"))
      (node (ref "IC1") (pin "8") (pinfunction "PGND_8") (pintype "passive"))
      (node (ref "IC4") (pin "2") (pinfunction "GND_2") (pintype "passive"))
      (node (ref "IC5") (pin "2") (pinfunction "GND_2") (pintype "passive"))
      (node (ref "IC6") (pin "2") (pinfunction "GND_2") (pintype "passive"))
      (node (ref "IC7") (pin "2") (pinfunction "-VS_2") (pintype "power_in"))
      (node (ref "J1") (pin "1") (pinfunction "1_1") (pintype "passive"))
      (node (ref "M3") (pin "1-2-3") (pinfunction "S_1-2-3") (pintype "passive"))
      (node (ref "M4") (pin "1-2-3") (pinfunction "S_1-2-3") (pintype "passive"))
      (node (ref "P2") (pin "1") (pinfunction "1_1") (pintype "passive"))
      (node (ref "R1") (pin "2") (pinfunction "2_2") (pintype "passive"))
      (node (ref "R11") (pin "1") (pinfunction "1_1") (pintype "passive"))
      (node (ref "R14") (pin "1") (pinfunction "1_1") (pintype "passive"))
      (node (ref "R19") (pin "1") (pinfunction "1_1") (pintype "passive"))
      (node (ref "R20") (pin "1") (pinfunction "1_1") (pintype "passive"))
      (node (ref "R21") (pin "2") (pinfunction "2_2") (pintype "passive"))
      (node (ref "R22") (pin "2") (pinfunction "2_2") (pintype "passive"))
      (node (ref "R27") (pin "1") (pinfunction "1_1") (pintype "passive"))
      (node (ref "R32") (pin "1") (pinfunction "1_1") (pintype "passive"))
      (node (ref "R35") (pin "2") (pinfunction "2_2") (pintype "passive"))
      (node (ref "R37") (pin "1") (pinfunction "1_1") (pintype "passive"))
      (node (ref "RT1") (pin "2") (pinfunction "2_2") (pintype "passive"))
      (node (ref "TP7") (pin "1") (pinfunction "TP_1") (pintype "passive"))
      (node (ref "TP8") (pin "1") (pinfunction "TP_1") (pintype "passive"))
      (node (ref "U1") (pin "3") (pinfunction "A_3") (pintype "passive"))
    )
    (net (code "21") (name "Net-(C49-Pad2)") (class "Default")
      (node (ref "C49") (pin "2") (pinfunction "2_2") (pintype "passive"))
      (node (ref "R31") (pin "1") (pinfunction "1_1") (pintype "passive"))
      (node (ref "R33") (pin "2") (pinfunction "2_2") (pintype "passive"))
    )
    (net (code "22") (name "Net-(C51-C1)") (class "Default")
      (node (ref "C51") (pin "1") (pinfunction "C1_1") (pintype "passive"))
      (node (ref "IC7") (pin "4") (pinfunction "-IN_4") (pintype "input"))
      (node (ref "R26") (pin "1") (pinfunction "1_1") (pintype "passive"))
      (node (ref "R35") (pin "1") (pinfunction "1_1") (pintype "passive"))
    )
    (net (code "23") (name "Net-(D1-K)") (class "Default")
      (node (ref "C24") (pin "2") (pinfunction "2_2") (pintype "passive"))
      (node (ref "D1") (pin "1") (pinfunction "K_1") (pintype "passive"))
      (node (ref "IC2") (pin "1") (pinfunction "VCC_1") (pintype "passive"))
    )
    (net (code "24") (name "Net-(D2-K)") (class "Default")
      (node (ref "C27") (pin "2") (pinfunction "2_2") (pintype "passive"))
      (node (ref "D2") (pin "1") (pinfunction "K_1") (pintype "passive"))
      (node (ref "IC3") (pin "1") (pinfunction "VCC_1") (pintype "passive"))
    )
    (net (code "25") (name "Net-(IC1-SS)") (class "Default")
      (node (ref "C28") (pin "2") (pinfunction "2_2") (pintype "passive"))
      (node (ref "IC1") (pin "5") (pinfunction "SS_5") (pintype "passive"))
    )
    (net (code "26") (name "Net-(IC2-GATE)") (class "Default")
      (node (ref "IC2") (pin "5") (pinfunction "GATE_5") (pintype "passive"))
      (node (ref "R5") (pin "1") (pinfunction "1_1") (pintype "passive"))
    )
    (net (code "27") (name "Net-(IC2-MOT)") (class "Default")
      (node (ref "IC2") (pin "3") (pinfunction "MOT_3") (pintype "passive"))
      (node (ref "R9") (pin "2") (pinfunction "2_2") (pintype "passive"))
    )
    (net (code "28") (name "Net-(IC2-VD)") (class "Default")
      (node (ref "C25") (pin "2") (pinfunction "2_2") (pintype "passive"))
      (node (ref "IC2") (pin "4") (pinfunction "VD_4") (pintype "passive"))
      (node (ref "R2") (pin "1") (pinfunction "1_1") (pintype "passive"))
    )
    (net (code "29") (name "Net-(IC3-GATE)") (class "Default")
      (node (ref "IC3") (pin "5") (pinfunction "GATE_5") (pintype "passive"))
      (node (ref "R6") (pin "1") (pinfunction "1_1") (pintype "passive"))
    )
    (net (code "30") (name "Net-(IC3-MOT)") (class "Default")
      (node (ref "IC3") (pin "3") (pinfunction "MOT_3") (pintype "passive"))
      (node (ref "R10") (pin "2") (pinfunction "2_2") (pintype "passive"))
    )
    (net (code "31") (name "Net-(IC3-VD)") (class "Default")
      (node (ref "C26") (pin "2") (pinfunction "2_2") (pintype "passive"))
      (node (ref "IC3") (pin "4") (pinfunction "VD_4") (pintype "passive"))
      (node (ref "R3") (pin "1") (pinfunction "1_1") (pintype "passive"))
    )
    (net (code "32") (name "Net-(IC4-GATE)") (class "Default")
      (node (ref "IC4") (pin "5") (pinfunction "GATE_5") (pintype "passive"))
      (node (ref "R17") (pin "1") (pinfunction "1_1") (pintype "passive"))
    )
    (net (code "33") (name "Net-(IC4-MOT)") (class "Default")
      (node (ref "IC4") (pin "3") (pinfunction "MOT_3") (pintype "passive"))
      (node (ref "R19") (pin "2") (pinfunction "2_2") (pintype "passive"))
    )
    (net (code "34") (name "Net-(IC4-VD)") (class "Default")
      (node (ref "C30") (pin "2") (pinfunction "2_2") (pintype "passive"))
      (node (ref "IC4") (pin "4") (pinfunction "VD_4") (pintype "passive"))
      (node (ref "R15") (pin "1") (pinfunction "1_1") (pintype "passive"))
    )
    (net (code "35") (name "Net-(IC5-GATE)") (class "Default")
      (node (ref "IC5") (pin "5") (pinfunction "GATE_5") (pintype "passive"))
      (node (ref "R18") (pin "1") (pinfunction "1_1") (pintype "passive"))
    )
    (net (code "36") (name "Net-(IC5-MOT)") (class "Default")
      (node (ref "IC5") (pin "3") (pinfunction "MOT_3") (pintype "passive"))
      (node (ref "R20") (pin "2") (pinfunction "2_2") (pintype "passive"))
    )
    (net (code "37") (name "Net-(IC5-VD)") (class "Default")
      (node (ref "C31") (pin "2") (pinfunction "2_2") (pintype "passive"))
      (node (ref "IC5") (pin "4") (pinfunction "VD_4") (pintype "passive"))
      (node (ref "R16") (pin "1") (pinfunction "1_1") (pintype "passive"))
    )
    (net (code "38") (name "Net-(IC6-+IN)") (class "Default")
      (node (ref "C43") (pin "2") (pinfunction "2_2") (pintype "passive"))
      (node (ref "C45") (pin "2") (pinfunction "2_2") (pintype "passive"))
      (node (ref "IC6") (pin "8") (pinfunction "+IN_8") (pintype "passive"))
      (node (ref "R28") (pin "1") (pinfunction "1_1") (pintype "passive"))
    )
    (net (code "39") (name "Net-(IC6--IN)") (class "Default")
      (node (ref "C43") (pin "1") (pinfunction "1_1") (pintype "passive"))
      (node (ref "C44") (pin "2") (pinfunction "2_2") (pintype "passive"))
      (node (ref "IC6") (pin "1") (pinfunction "-IN_1") (pintype "passive"))
      (node (ref "R29") (pin "1") (pinfunction "1_1") (pintype "passive"))
    )
    (net (code "40") (name "Net-(IC7-+IN)") (class "Default")
      (node (ref "IC7") (pin "3") (pinfunction "+IN_3") (pintype "input"))
      (node (ref "R33") (pin "1") (pinfunction "1_1") (pintype "passive"))
    )
    (net (code "41") (name "Net-(LED1-K)") (class "Default")
      (node (ref "LED1") (pin "1") (pinfunction "K_1") (pintype "passive"))
      (node (ref "R1") (pin "1") (pinfunction "1_1") (pintype "passive"))
    )
    (net (code "42") (name "Net-(M1-G)") (class "Default")
      (node (ref "M1") (pin "4") (pinfunction "G_4") (pintype "passive"))
      (node (ref "R13") (pin "1") (pinfunction "1_1") (pintype "passive"))
      (node (ref "R6") (pin "2") (pinfunction "2_2") (pintype "passive"))
      (node (ref "TP2") (pin "1") (pinfunction "TP_1") (pintype "passive"))
    )
    (net (code "43") (name "Net-(M2-G)") (class "Default")
      (node (ref "M2") (pin "4") (pinfunction "G_4") (pintype "passive"))
      (node (ref "R12") (pin "1") (pinfunction "1_1") (pintype "passive"))
      (node (ref "R5") (pin "2") (pinfunction "2_2") (pintype "passive"))
      (node (ref "TP1") (pin "1") (pinfunction "TP_1") (pintype "passive"))
    )
    (net (code "44") (name "Net-(M3-G)") (class "Default")
      (node (ref "M3") (pin "4") (pinfunction "G_4") (pintype "passive"))
      (node (ref "R18") (pin "2") (pinfunction "2_2") (pintype "passive"))
      (node (ref "R22") (pin "1") (pinfunction "1_1") (pintype "passive"))
      (node (ref "TP6") (pin "1") (pinfunction "TP_1") (pintype "passive"))
    )
    (net (code "45") (name "Net-(M4-G)") (class "Default")
      (node (ref "M4") (pin "4") (pinfunction "G_4") (pintype "passive"))
      (node (ref "R17") (pin "2") (pinfunction "2_2") (pintype "passive"))
      (node (ref "R21") (pin "1") (pinfunction "1_1") (pintype "passive"))
      (node (ref "TP5") (pin "1") (pinfunction "TP_1") (pintype "passive"))
    )
    (net (code "46") (name "Net-(TP11-TP)") (class "Default")
      (node (ref "C40") (pin "2") (pinfunction "2_2") (pintype "passive"))
      (node (ref "R24") (pin "1") (pinfunction "1_1") (pintype "passive"))
      (node (ref "R27") (pin "2") (pinfunction "2_2") (pintype "passive"))
      (node (ref "TP11") (pin "1") (pinfunction "TP_1") (pintype "passive"))
      (node (ref "U1") (pin "1") (pinfunction "REF_1") (pintype "input"))
    )
    (net (code "47") (name "unconnected-(IC6-NC_1-Pad3)") (class "Default")
      (node (ref "IC6") (pin "3") (pinfunction "NC_1_3") (pintype "passive+no_connect"))
    )
    (net (code "48") (name "unconnected-(IC6-NC_2-Pad4)") (class "Default")
      (node (ref "IC6") (pin "4") (pinfunction "NC_2_4") (pintype "passive+no_connect"))
    )
    (net (code "49") (name "unconnected-(IC6-NC_3-Pad7)") (class "Default")
      (node (ref "IC6") (pin "7") (pinfunction "NC_3_7") (pintype "passive+no_connect"))
    )
    (net (code "50") (name "unconnected-(J1-Pad2)") (class "Default")
      (node (ref "J1") (pin "2") (pinfunction "2_2") (pintype "passive+no_connect"))
    )
    (net (code "51") (name "unconnected-(J1-Pad3)") (class "Default")
      (node (ref "J1") (pin "3") (pinfunction "3_3") (pintype "passive+no_connect"))
    )
    (net (code "52") (name "unconnected-(J1-Pad4)") (class "Default")
      (node (ref "J1") (pin "4") (pinfunction "4_4") (pintype "passive+no_connect"))
    )
    (net (code "53") (name "unconnected-(J1-Pad5)") (class "Default")
      (node (ref "J1") (pin "5") (pinfunction "5_5") (pintype "passive+no_connect"))
    )
    (net (code "54") (name "unconnected-(J1-Pad6)") (class "Default")
      (node (ref "J1") (pin "6") (pinfunction "6_6") (pintype "passive+no_connect"))
    )
    (net (code "55") (name "unconnected-(J1-Pad7)") (class "Default")
      (node (ref "J1") (pin "7") (pinfunction "7_7") (pintype "passive+no_connect"))
    )
    (net (code "56") (name "unconnected-(J1-Pad8)") (class "Default")
      (node (ref "J1") (pin "8") (pinfunction "8_8") (pintype "passive+no_connect"))
    )
    (net (code "57") (name "unconnected-(J1-Pad9)") (class "Default")
      (node (ref "J1") (pin "9") (pinfunction "9_9") (pintype "passive+no_connect"))
    )
    (net (code "58") (name "unconnected-(J1-Pad10)") (class "Default")
      (node (ref "J1") (pin "10") (pinfunction "10_10") (pintype "passive+no_connect"))
    )
    (net (code "59") (name "unconnected-(J1-Pad11)") (class "Default")
      (node (ref "J1") (pin "11") (pinfunction "11_11") (pintype "passive+no_connect"))
    )
    (net (code "60") (name "unconnected-(J1-Pad12)") (class "Default")
      (node (ref "J1") (pin "12") (pinfunction "12_12") (pintype "passive+no_connect"))
    )
    (net (code "61") (name "unconnected-(J1-Pad13)") (class "Default")
      (node (ref "J1") (pin "13") (pinfunction "13_13") (pintype "passive+no_connect"))
    )
    (net (code "62") (name "unconnected-(J1-Pad14)") (class "Default")
      (node (ref "J1") (pin "14") (pinfunction "14_14") (pintype "passive+no_connect"))
    )
    (net (code "63") (name "unconnected-(J2-Pad2)") (class "Default")
      (node (ref "J2") (pin "2") (pinfunction "2_2") (pintype "passive+no_connect"))
    )
    (net (code "64") (name "unconnected-(J2-Pad3)") (class "Default")
      (node (ref "J2") (pin "3") (pinfunction "3_3") (pintype "passive+no_connect"))
    )
    (net (code "65") (name "unconnected-(J2-Pad4)") (class "Default")
      (node (ref "J2") (pin "4") (pinfunction "4_4") (pintype "passive+no_connect"))
    )
    (net (code "66") (name "unconnected-(J2-Pad5)") (class "Default")
      (node (ref "J2") (pin "5") (pinfunction "5_5") (pintype "passive+no_connect"))
    )
    (net (code "67") (name "unconnected-(J2-Pad6)") (class "Default")
      (node (ref "J2") (pin "6") (pinfunction "6_6") (pintype "passive+no_connect"))
    )
    (net (code "68") (name "unconnected-(J2-Pad7)") (class "Default")
      (node (ref "J2") (pin "7") (pinfunction "7_7") (pintype "passive+no_connect"))
    )
    (net (code "69") (name "unconnected-(J2-Pad8)") (class "Default")
      (node (ref "J2") (pin "8") (pinfunction "8_8") (pintype "passive+no_connect"))
    )
    (net (code "70") (name "unconnected-(J2-Pad9)") (class "Default")
      (node (ref "J2") (pin "9") (pinfunction "9_9") (pintype "passive+no_connect"))
    )
    (net (code "71") (name "unconnected-(J2-Pad10)") (class "Default")
      (node (ref "J2") (pin "10") (pinfunction "10_10") (pintype "passive+no_connect"))
    )
    (net (code "72") (name "unconnected-(J2-Pad11)") (class "Default")
      (node (ref "J2") (pin "11") (pinfunction "11_11") (pintype "passive+no_connect"))
    )
    (net (code "73") (name "unconnected-(J2-Pad12)") (class "Default")
      (node (ref "J2") (pin "12") (pinfunction "12_12") (pintype "passive+no_connect"))
    )
    (net (code "74") (name "unconnected-(J2-Pad13)") (class "Default")
      (node (ref "J2") (pin "13") (pinfunction "13_13") (pintype "passive+no_connect"))
    )
    (net (code "75") (name "unconnected-(J2-Pad14)") (class "Default")
      (node (ref "J2") (pin "14") (pinfunction "14_14") (pintype "passive+no_connect"))
    )
    (net (code "76") (name "unconnected-(J2-Pad15)") (class "Default")
      (node (ref "J2") (pin "15") (pinfunction "15_15") (pintype "passive+no_connect"))
    )
    (net (code "77") (name "unconnected-(J2-Pad16)") (class "Default")
      (node (ref "J2") (pin "16") (pinfunction "16_16") (pintype "passive+no_connect"))
    )
    (net (code "78") (name "unconnected-(J2-Pad17)") (class "Default")
      (node (ref "J2") (pin "17") (pinfunction "17_17") (pintype "passive+no_connect"))
    )
    (net (code "79") (name "unconnected-(M5-Pad1)") (class "Default")
      (node (ref "M5") (pin "1") (pinfunction "1_1") (pintype "passive+no_connect"))
    )
    (net (code "80") (name "unconnected-(M6-Pad1)") (class "Default")
      (node (ref "M6") (pin "1") (pinfunction "1_1") (pintype "passive+no_connect"))
    )
    (net (code "81") (name "unconnected-(M7-Pad1)") (class "Default")
      (node (ref "M7") (pin "1") (pinfunction "1_1") (pintype "passive+no_connect"))
    )
    (net (code "82") (name "unconnected-(M8-Pad1)") (class "Default")
      (node (ref "M8") (pin "1") (pinfunction "1_1") (pintype "passive+no_connect"))
    )
    (net (code "83") (name "unconnected-(R37-Pad3)") (class "Default")
      (node (ref "R37") (pin "3") (pinfunction "3_3") (pintype "passive+no_connect"))
    )
  )
)
